# Microcontroller_STM32F04.net
KiCad netlist of a schematic drawn in Altium Designer
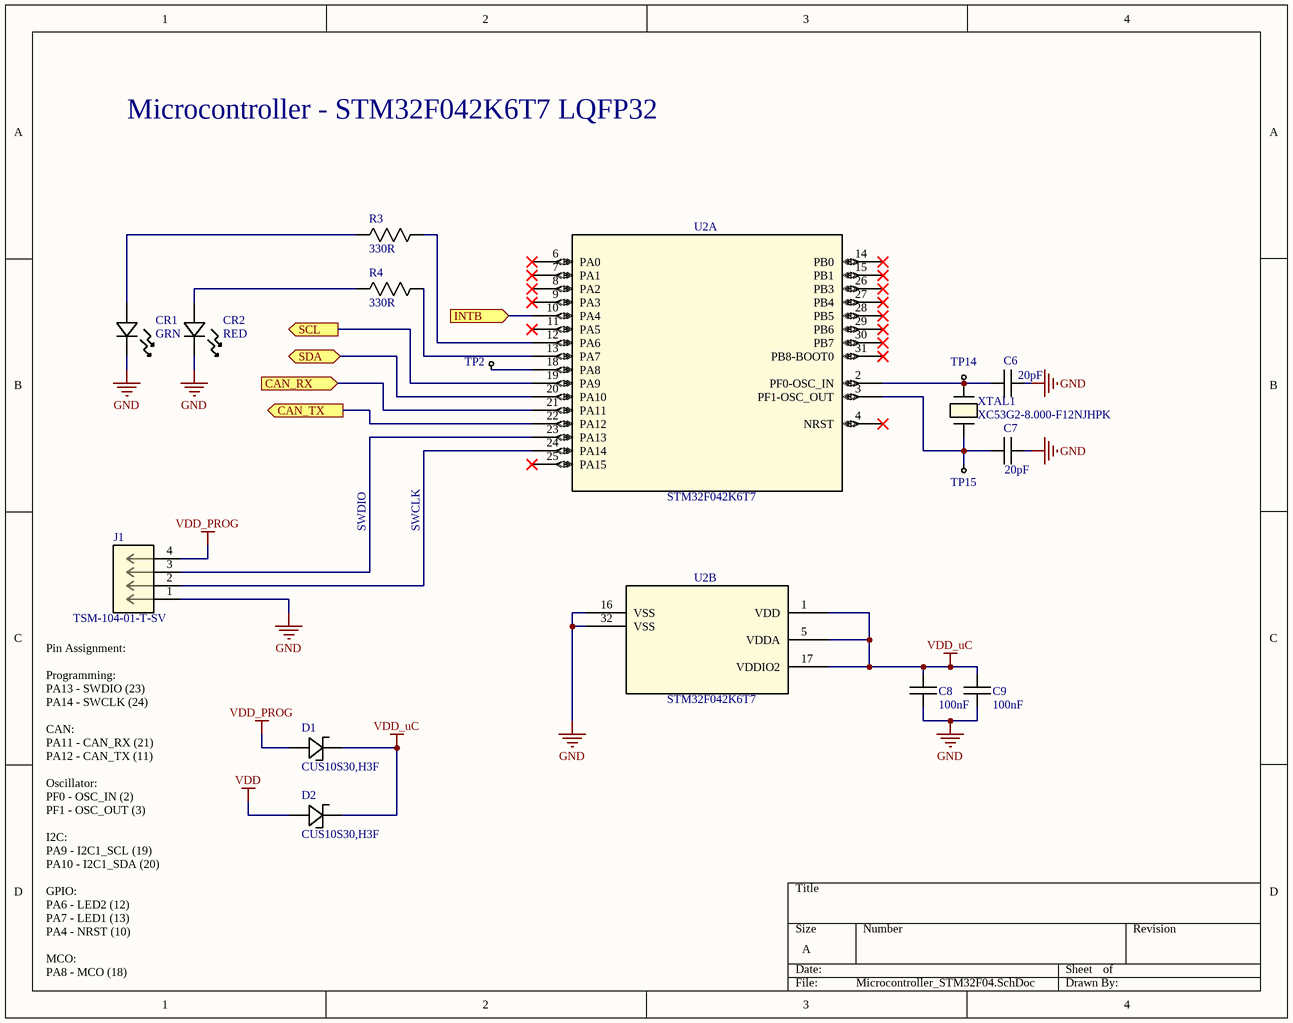
[diagram p0: Microcontroller_STM32F04.SchDoc]

(export (version "E")
  (design (tool "Eeschema 10.0.6"))
  (components
    (comp (ref "C6")
      (value "20pF")
      (footprint "C0603")
      (description "Multilayer Ceramic Capacitor, 20 pF, 50 V, ± 5%, C0G (NP0), 0603 [1608 Metric]")
      (fields
        (field (name "MANUFACTURER") "Samsung")
        (field (name "MANUFACTURER PART NUMBER") "CL10C200JB8NNNC")
      )
      (libsource (lib "Schlib1") (part "CL10C200JB8NNNC"))
    )
    (comp (ref "C7")
      (value "20pF")
      (footprint "C0603")
      (description "Multilayer Ceramic Capacitor, 20 pF, 50 V, ± 5%, C0G (NP0), 0603 [1608 Metric]")
      (fields
        (field (name "MANUFACTURER") "Samsung")
        (field (name "MANUFACTURER PART NUMBER") "CL10C200JB8NNNC")
      )
      (libsource (lib "Schlib1") (part "CL10C200JB8NNNC"))
    )
    (comp (ref "C8")
      (value "100nF")
      (footprint "CAP0805")
      (description "Multilayer Ceramic Capacitor, 0.1 uF, 50 V, ± 10%, X7R, 0805 [2012 Metric]")
      (fields
        (field (name "MANUFACTURER") "Yageo")
        (field (name "MANUFACTURER PART NUMBER") "CC0805KRX7R9BB104")
      )
      (libsource (lib "Schlib1") (part "CC0805KRX7R9BB104"))
    )
    (comp (ref "C9")
      (value "100nF")
      (footprint "CAP0805")
      (description "Multilayer Ceramic Capacitor, 0.1 uF, 50 V, ± 10%, X7R, 0805 [2012 Metric]")
      (fields
        (field (name "MANUFACTURER") "Yageo")
        (field (name "MANUFACTURER PART NUMBER") "CC0805KRX7R9BB104")
      )
      (libsource (lib "Schlib1") (part "CC0805KRX7R9BB104"))
    )
    (comp (ref "CR1")
      (value "GRN")
      (footprint "LED_VISHAY_VLMX1300_VIS")
      (description "LED Uni-Color Yellow Green 574nm 2-Pin Chip 0603(1608Metric) T/R")
      (fields
        (field (name "MANUFACTURER_PART_NUMBER") "VLMG1300-GS08")
        (field (name "MANUFACTURER") "Vishay Semiconductors")
        (field (name "COPYRIGHT") "Copyright (C) 2023 Ultra Librarian. All rights reserved.")
      )
      (libsource (lib "Schlib1") (part "VLMG1300-GS08"))
    )
    (comp (ref "CR2")
      (value "RED")
      (footprint "LED_VISHAY_VLMX1300_VIS")
      (description "LED RED 0603 SMD")
      (fields
        (field (name "MANUFACTURER_PART_NUMBER") "VLMS1300-GS08")
        (field (name "MANUFACTURER") "Vishay Semiconductors")
        (field (name "COPYRIGHT") "Copyright (C) 2023 Ultra Librarian. All rights reserved.")
      )
      (libsource (lib "Schlib1") (part "VLMS1300-GS08"))
    )
    (comp (ref "D1")
      (value "CUS10S30,H3F")
      (footprint "USC_TOS")
      (description "Rectifier Diode, Schottky, 1 Phase, 1 Element, 1A, 30V V(RRM), Silicon")
      (fields
        (field (name "MANUFACTURER") "Toshiba")
        (field (name "LCSC PART#") "C146335")
        (field (name "COPYRIGHT") "Copyright (C) 2023 Ultra Librarian. All rights reserved.")
      )
      (libsource (lib "Schlib1") (part "CUS10S30,H3F"))
    )
    (comp (ref "D2")
      (value "CUS10S30,H3F")
      (footprint "USC_TOS")
      (description "Rectifier Diode, Schottky, 1 Phase, 1 Element, 1A, 30V V(RRM), Silicon")
      (fields
        (field (name "MANUFACTURER") "Toshiba")
        (field (name "LCSC PART#") "C146335")
        (field (name "COPYRIGHT") "Copyright (C) 2023 Ultra Librarian. All rights reserved.")
      )
      (libsource (lib "Schlib1") (part "CUS10S30,H3F"))
    )
    (comp (ref "J1")
      (value "TSM-104-01-T-SV")
      (footprint "CONN_TSM-104-01-T-SV_SAI")
      (description "Conn Unshrouded Header HDR 4 POS 2.54mm Solder ST Top Entry SMD Tube")
      (fields
        (field (name "MANUFACTURER") "Samtec")
        (field (name "LCSC PART#") "C3335977")
        (field (name "COPYRIGHT") "Copyright (C) 2023 Ultra Librarian. All rights reserved.")
      )
      (libsource (lib "Schlib1") (part "TSM-104-01-T-SV"))
    )
    (comp (ref "R3")
      (value "330R")
      (footprint "R0603")
      (description "Res Thick Film 0603 330 Ohm 5% 0.1W(1/10W) ±100ppm/C Pad SMD T/R")
      (fields
        (field (name "MANUFACTURER") "Yageo")
        (field (name "MANUFACTURER PART NUMBER") "RC0603JR-13330RL")
      )
      (libsource (lib "Schlib1") (part "RC0603JR-13330RL"))
    )
    (comp (ref "R4")
      (value "330R")
      (footprint "R0603")
      (description "Res Thick Film 0603 330 Ohm 5% 0.1W(1/10W) ±100ppm/C Pad SMD T/R")
      (fields
        (field (name "MANUFACTURER") "Yageo")
        (field (name "MANUFACTURER PART NUMBER") "RC0603JR-13330RL")
      )
      (libsource (lib "Schlib1") (part "RC0603JR-13330RL"))
    )
    (comp (ref "TP2")
      (value "1mm Test Point")
      (footprint "TP_1MM")
      (libsource (lib "Schlib1") (part "TestPoint_1mm"))
    )
    (comp (ref "TP14")
      (value "1mm Test Point")
      (footprint "TP_1MM")
      (libsource (lib "Schlib1") (part "TestPoint_1mm"))
    )
    (comp (ref "TP15")
      (value "1mm Test Point")
      (footprint "TP_1MM")
      (libsource (lib "Schlib1") (part "TestPoint_1mm"))
    )
    (comp (ref "U2")
      (value "STM32F042K6T7")
      (footprint "LQFP-32")
      (description "ARM® Cortex®-M0 STM32 F0 Microcontroller IC 32-Bit 48MHz 32KB (32K x 8) FLASH 32-LQFP (7x7)")
      (fields
        (field (name "MANUFACTURER") "STMicroelectronics")
        (field (name "LCSC PART#") "C1337340")
        (field (name "COPYRIGHT") "Copyright (C) 2023 Ultra Librarian. All rights reserved.")
      )
      (libsource (lib "Schlib1") (part "STM32F042K6T7"))
    )
    (comp (ref "XTAL1")
      (value "XC53G2-8.000-F12NJHPK")
      (footprint "XTAL_NX5032_NDK")
      (description "CRYSTAL 8MHZ 12PF SMD")
      (fields
        (field (name "LCSC PART#") "C2842269")
        (field (name "COPYRIGHT") "Copyright (C) 2023 Ultra Librarian. All rights reserved.")
      )
      (libsource (lib "Schlib1") (part "XC53G2-8.000-F12NJHP"))
    )
  )
  (nets
    (net (code "1") (name "/CAN_RX") (class "Default")
      (node (ref "U2") (pin "21") (pinfunction "PA11_21") (pintype "bidirectional"))
    )
    (net (code "2") (name "/CAN_TX") (class "Default")
      (node (ref "U2") (pin "22") (pinfunction "PA12_22") (pintype "bidirectional"))
    )
    (net (code "3") (name "/INTB") (class "Default")
      (node (ref "U2") (pin "10") (pinfunction "PA4_10") (pintype "bidirectional"))
    )
    (net (code "4") (name "/SCL") (class "Default")
      (node (ref "U2") (pin "19") (pinfunction "PA9_19") (pintype "bidirectional"))
    )
    (net (code "5") (name "/SDA") (class "Default")
      (node (ref "U2") (pin "20") (pinfunction "PA10_20") (pintype "bidirectional"))
    )
    (net (code "6") (name "GND") (class "Default")
      (node (ref "C6") (pin "1") (pinfunction "1_1") (pintype "passive"))
      (node (ref "C7") (pin "1") (pinfunction "1_1") (pintype "passive"))
      (node (ref "C8") (pin "2") (pinfunction "2_2") (pintype "passive"))
      (node (ref "C9") (pin "2") (pinfunction "2_2") (pintype "passive"))
      (node (ref "CR1") (pin "1") (pinfunction "1_1") (pintype "passive"))
      (node (ref "CR2") (pin "1") (pinfunction "1_1") (pintype "passive"))
      (node (ref "J1") (pin "1") (pinfunction "1_1") (pintype "passive"))
      (node (ref "U2") (pin "16") (pinfunction "VSS_16") (pintype "power_in"))
      (node (ref "U2") (pin "32") (pinfunction "VSS_32") (pintype "power_in"))
    )
    (net (code "7") (name "Net-(CR1-Pad2)") (class "Default")
      (node (ref "CR1") (pin "2") (pinfunction "2_2") (pintype "passive"))
      (node (ref "R3") (pin "2") (pinfunction "2_2") (pintype "passive"))
    )
    (net (code "8") (name "Net-(CR2-Pad2)") (class "Default")
      (node (ref "CR2") (pin "2") (pinfunction "2_2") (pintype "passive"))
      (node (ref "R4") (pin "2") (pinfunction "2_2") (pintype "passive"))
    )
    (net (code "9") (name "Net-(TP2-0)") (class "Default")
      (node (ref "TP2") (pin "1") (pinfunction "0_1") (pintype "passive"))
      (node (ref "U2") (pin "18") (pinfunction "PA8_18") (pintype "bidirectional"))
    )
    (net (code "10") (name "Net-(TP14-0)") (class "Default")
      (node (ref "C6") (pin "2") (pinfunction "2_2") (pintype "passive"))
      (node (ref "TP14") (pin "1") (pinfunction "0_1") (pintype "passive"))
      (node (ref "U2") (pin "2") (pinfunction "PF0-OSC_IN_2") (pintype "bidirectional"))
      (node (ref "XTAL1") (pin "2") (pinfunction "2_2") (pintype "passive"))
    )
    (net (code "11") (name "Net-(TP15-0)") (class "Default")
      (node (ref "C7") (pin "2") (pinfunction "2_2") (pintype "passive"))
      (node (ref "TP15") (pin "1") (pinfunction "0_1") (pintype "passive"))
      (node (ref "U2") (pin "3") (pinfunction "PF1-OSC_OUT_3") (pintype "bidirectional"))
      (node (ref "XTAL1") (pin "1") (pinfunction "1_1") (pintype "passive"))
    )
    (net (code "12") (name "Net-(U2A-PA6)") (class "Default")
      (node (ref "R3") (pin "1") (pinfunction "1_1") (pintype "passive"))
      (node (ref "U2") (pin "12") (pinfunction "PA6_12") (pintype "bidirectional"))
    )
    (net (code "13") (name "Net-(U2A-PA7)") (class "Default")
      (node (ref "R4") (pin "1") (pinfunction "1_1") (pintype "passive"))
      (node (ref "U2") (pin "13") (pinfunction "PA7_13") (pintype "bidirectional"))
    )
    (net (code "14") (name "Net-(U2A-PA13)") (class "Default")
      (node (ref "J1") (pin "3") (pinfunction "3_3") (pintype "passive"))
      (node (ref "U2") (pin "23") (pinfunction "PA13_23") (pintype "bidirectional"))
    )
    (net (code "15") (name "Net-(U2A-PA14)") (class "Default")
      (node (ref "J1") (pin "2") (pinfunction "2_2") (pintype "passive"))
      (node (ref "U2") (pin "24") (pinfunction "PA14_24") (pintype "bidirectional"))
    )
    (net (code "16") (name "VDD") (class "Default")
      (node (ref "D2") (pin "2") (pinfunction "anode_2") (pintype "passive"))
    )
    (net (code "17") (name "VDD_PROG") (class "Default")
      (node (ref "D1") (pin "2") (pinfunction "anode_2") (pintype "passive"))
      (node (ref "J1") (pin "4") (pinfunction "4_4") (pintype "passive"))
    )
    (net (code "18") (name "VDD_uC") (class "Default")
      (node (ref "C8") (pin "1") (pinfunction "1_1") (pintype "passive"))
      (node (ref "C9") (pin "1") (pinfunction "1_1") (pintype "passive"))
      (node (ref "D1") (pin "1") (pinfunction "cathode_1") (pintype "passive"))
      (node (ref "D2") (pin "1") (pinfunction "cathode_1") (pintype "passive"))
      (node (ref "U2") (pin "1") (pinfunction "VDD_1") (pintype "power_in"))
      (node (ref "U2") (pin "17") (pinfunction "VDDIO2_17") (pintype "power_in"))
      (node (ref "U2") (pin "5") (pinfunction "VDDA_5") (pintype "power_in"))
    )
    (net (code "19") (name "unconnected-(U2A-NRST-Pad4)") (class "Default")
      (node (ref "U2") (pin "4") (pinfunction "NRST_4") (pintype "bidirectional+no_connect"))
    )
    (net (code "20") (name "unconnected-(U2A-PA0-Pad6)") (class "Default")
      (node (ref "U2") (pin "6") (pinfunction "PA0_6") (pintype "bidirectional+no_connect"))
    )
    (net (code "21") (name "unconnected-(U2A-PA1-Pad7)") (class "Default")
      (node (ref "U2") (pin "7") (pinfunction "PA1_7") (pintype "bidirectional+no_connect"))
    )
    (net (code "22") (name "unconnected-(U2A-PA2-Pad8)") (class "Default")
      (node (ref "U2") (pin "8") (pinfunction "PA2_8") (pintype "bidirectional+no_connect"))
    )
    (net (code "23") (name "unconnected-(U2A-PA3-Pad9)") (class "Default")
      (node (ref "U2") (pin "9") (pinfunction "PA3_9") (pintype "bidirectional+no_connect"))
    )
    (net (code "24") (name "unconnected-(U2A-PA5-Pad11)") (class "Default")
      (node (ref "U2") (pin "11") (pinfunction "PA5_11") (pintype "bidirectional+no_connect"))
    )
    (net (code "25") (name "unconnected-(U2A-PA15-Pad25)") (class "Default")
      (node (ref "U2") (pin "25") (pinfunction "PA15_25") (pintype "bidirectional+no_connect"))
    )
    (net (code "26") (name "unconnected-(U2A-PB0-Pad14)") (class "Default")
      (node (ref "U2") (pin "14") (pinfunction "PB0_14") (pintype "bidirectional+no_connect"))
    )
    (net (code "27") (name "unconnected-(U2A-PB1-Pad15)") (class "Default")
      (node (ref "U2") (pin "15") (pinfunction "PB1_15") (pintype "bidirectional+no_connect"))
    )
    (net (code "28") (name "unconnected-(U2A-PB3-Pad26)") (class "Default")
      (node (ref "U2") (pin "26") (pinfunction "PB3_26") (pintype "bidirectional+no_connect"))
    )
    (net (code "29") (name "unconnected-(U2A-PB4-Pad27)") (class "Default")
      (node (ref "U2") (pin "27") (pinfunction "PB4_27") (pintype "bidirectional+no_connect"))
    )
    (net (code "30") (name "unconnected-(U2A-PB5-Pad28)") (class "Default")
      (node (ref "U2") (pin "28") (pinfunction "PB5_28") (pintype "bidirectional+no_connect"))
    )
    (net (code "31") (name "unconnected-(U2A-PB6-Pad29)") (class "Default")
      (node (ref "U2") (pin "29") (pinfunction "PB6_29") (pintype "bidirectional+no_connect"))
    )
    (net (code "32") (name "unconnected-(U2A-PB7-Pad30)") (class "Default")
      (node (ref "U2") (pin "30") (pinfunction "PB7_30") (pintype "bidirectional+no_connect"))
    )
    (net (code "33") (name "unconnected-(U2A-PB8-BOOT0-Pad31)") (class "Default")
      (node (ref "U2") (pin "31") (pinfunction "PB8-BOOT0_31") (pintype "bidirectional+no_connect"))
    )
  )
)
